# Connectors.net
KiCad netlist of a schematic drawn in Altium Designer
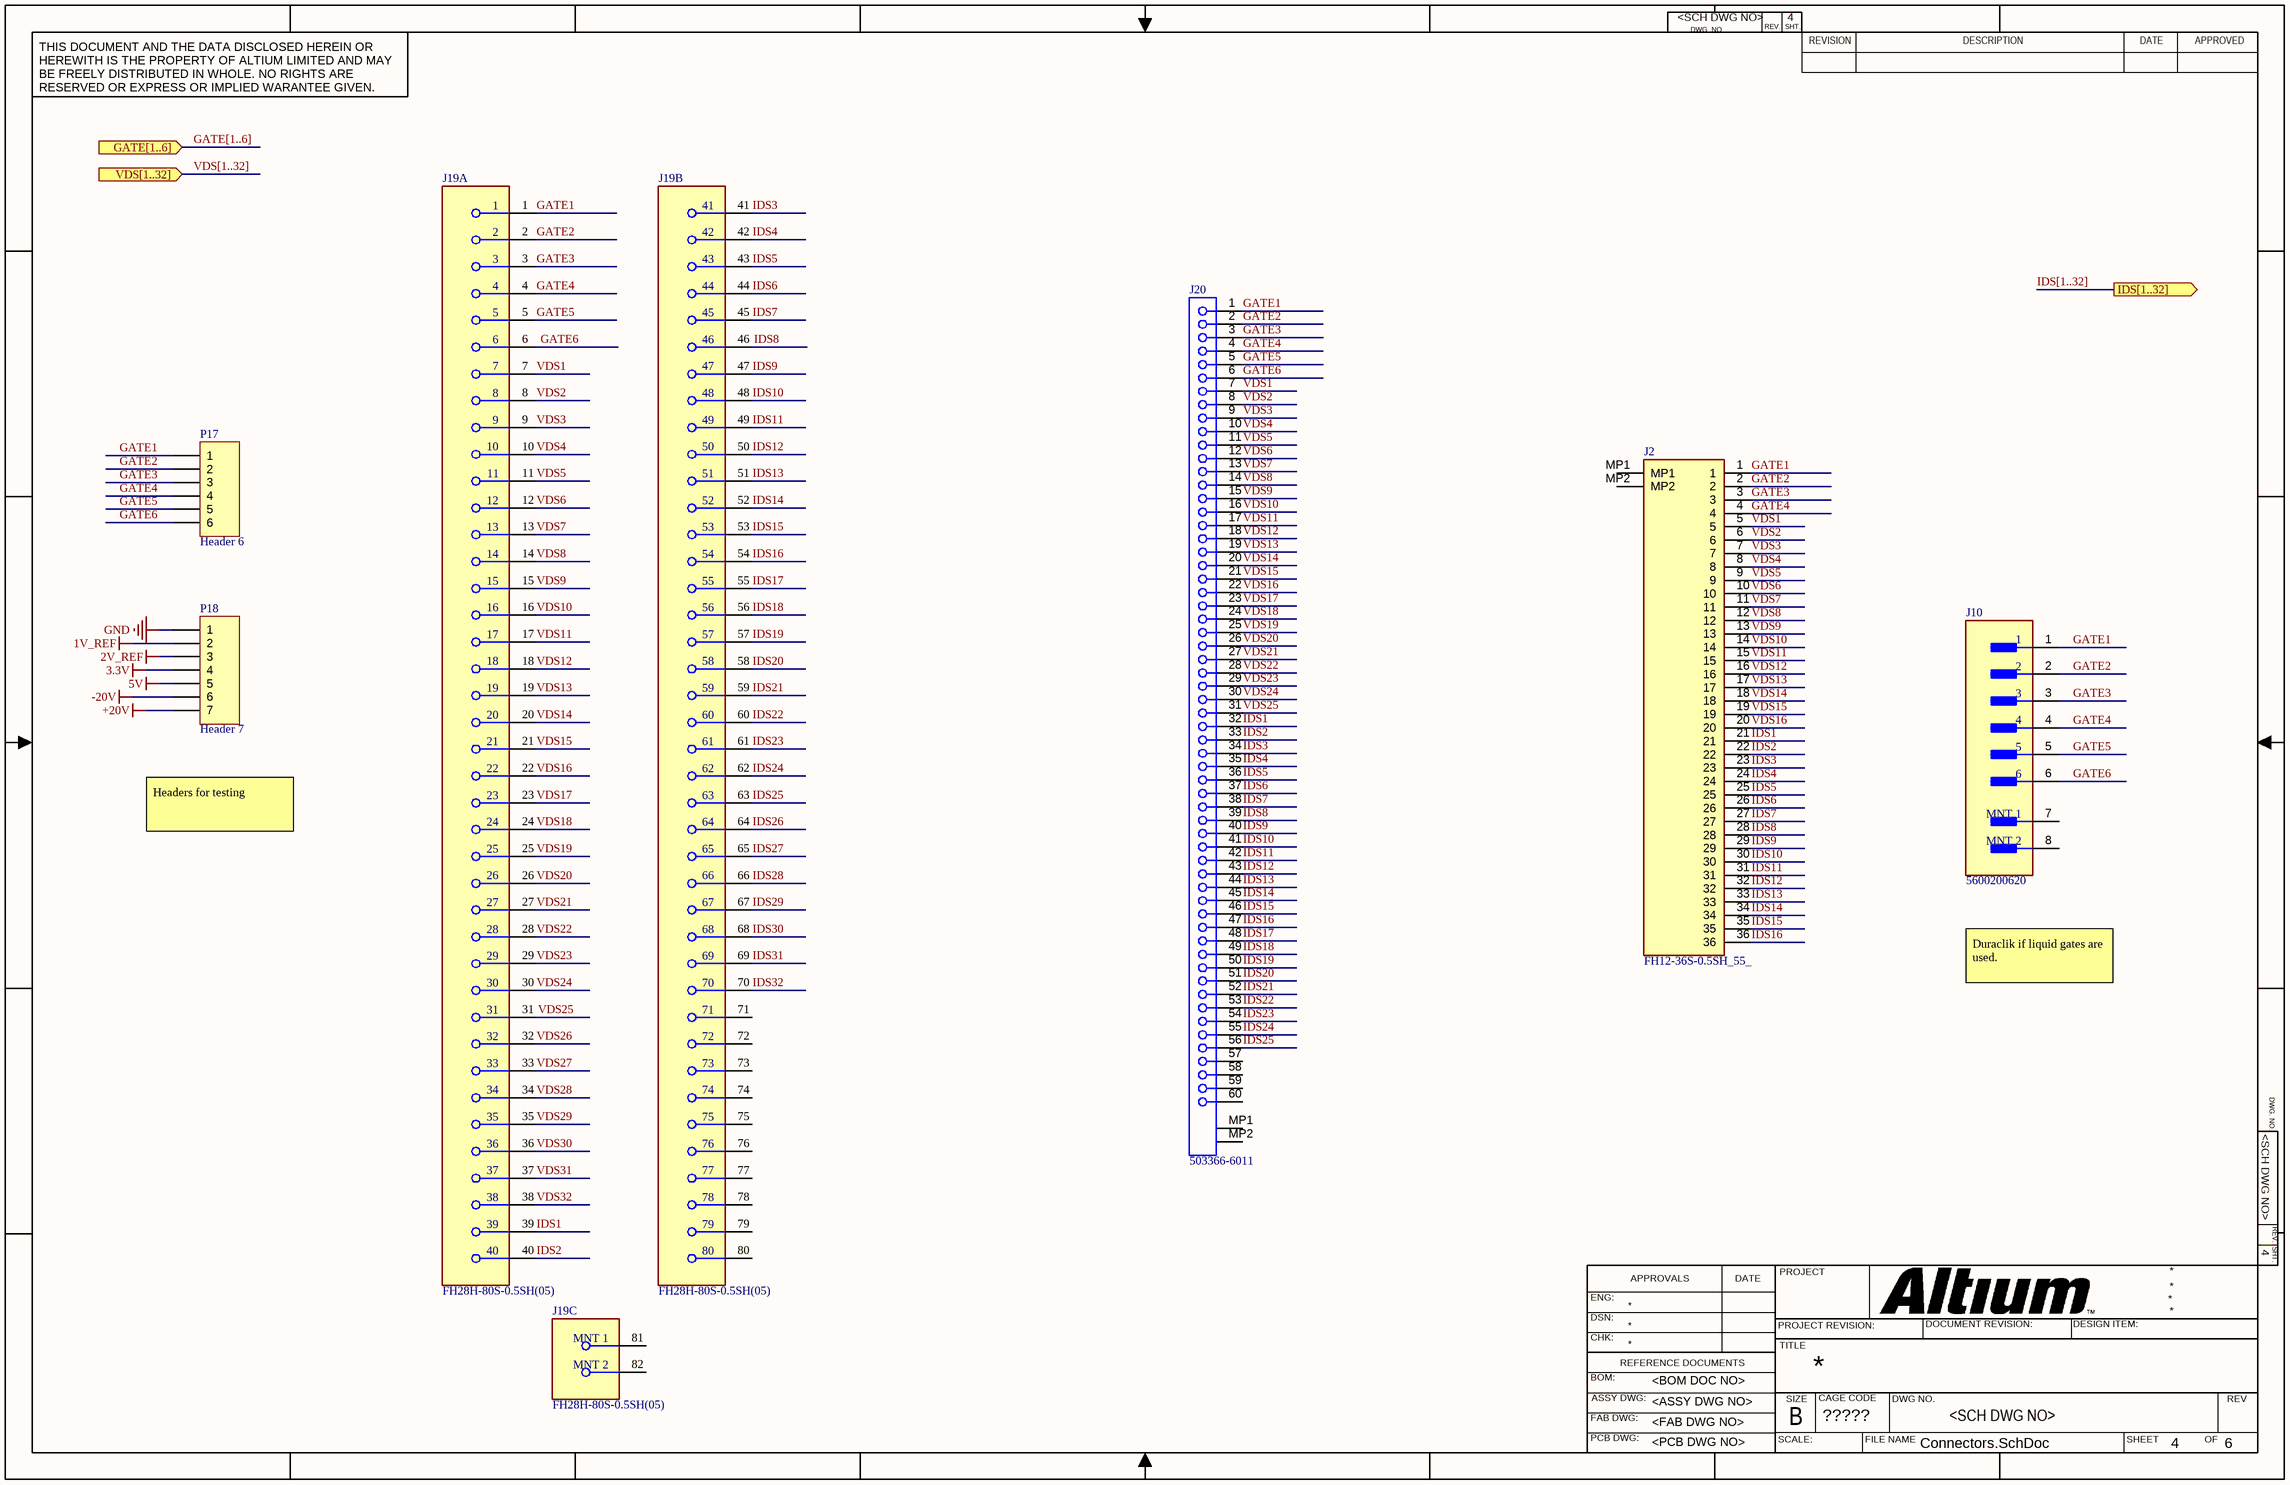
[diagram p0: Connectors.SchDoc]

(export (version "E")
  (design (tool "Eeschema 10.0.6"))
  (components
    (comp (ref "J2")
      (value "FH12-36S-0.5SH_55_")
      (footprint "FH1236S05SH55")
      (description "Connector")
      (fields
        (field (name "MANUFACTURER_PART_NUMBER") "FH12-36S-0.5SH(55)")
        (field (name "MOUSER PART NUMBER") "798-FH12-36S-0.5SH55")
      )
      (libsource (lib "SamacSys") (part "FH12-36S-0.5SH_55_"))
    )
    (comp (ref "J10")
      (value "5600200620")
      (footprint "FP-5600200620-MFG")
      (description "CONN HEADER SMD 6POS 2MM")
      (fields
        (field (name "OCTOPART") "https://octopart.com/5600200620-molex-51767481")
        (field (name "MANUFACTURER") "Molex")
      )
      (libsource (lib "Altium Content Vault") (part "ed24c53d9ba001d1a2a686240a95171"))
    )
    (comp (ref "J19")
      (value "FH28H-80S-0.5SH(05)")
      (footprint "FP-FH28H-80S-0_5SH_05-MFG")
      (description "CONN FFC BOTTOM 80POS 0.50MM R/A")
      (libsource (lib "Altium Content Vault") (part "08075b3669470a400ec152efcfe4938"))
    )
    (comp (ref "J20")
      (value "503366-6011")
      (footprint "MOLX-503366-6011")
      (fields (field (name "MANUFACTURER") "Molex"))
      (libsource (lib "Altium Content Vault") (part "MOLX-503366-6011"))
    )
    (comp (ref "P17")
      (value "Header 6")
      (footprint "HDR1X6")
      (description "Header, 6-Pin")
      (fields (field (name "PUBLISHER") "Altium Limited"))
      (libsource (lib "Miscellaneous Connectors") (part "Header 6"))
    )
    (comp (ref "P18")
      (value "Header 7")
      (footprint "HDR1X7")
      (description "Header, 7-Pin")
      (fields (field (name "PUBLISHER") "Altium Limited"))
      (libsource (lib "Miscellaneous Connectors") (part "Header 7"))
    )
  )
  (nets
    (net (code "1") (name "+20V") (class "Default")
      (node (ref "P18") (pin "7") (pinfunction "7_7") (pintype "passive"))
    )
    (net (code "2") (name "-20V") (class "Default")
      (node (ref "P18") (pin "6") (pinfunction "6_6") (pintype "passive"))
    )
    (net (code "3") (name "/GATE1") (class "Default")
      (node (ref "J10") (pin "1") (pinfunction "1_1") (pintype "passive"))
      (node (ref "J19") (pin "1") (pinfunction "1_1") (pintype "passive"))
      (node (ref "J2") (pin "1") (pinfunction "1_1") (pintype "passive"))
      (node (ref "J20") (pin "1") (pinfunction "1_1") (pintype "passive"))
      (node (ref "P17") (pin "1") (pinfunction "1_1") (pintype "passive"))
    )
    (net (code "4") (name "/GATE2") (class "Default")
      (node (ref "J10") (pin "2") (pinfunction "2_2") (pintype "passive"))
      (node (ref "J19") (pin "2") (pinfunction "2_2") (pintype "passive"))
      (node (ref "J2") (pin "2") (pinfunction "2_2") (pintype "passive"))
      (node (ref "J20") (pin "2") (pinfunction "2_2") (pintype "passive"))
      (node (ref "P17") (pin "2") (pinfunction "2_2") (pintype "passive"))
    )
    (net (code "5") (name "/GATE3") (class "Default")
      (node (ref "J10") (pin "3") (pinfunction "3_3") (pintype "passive"))
      (node (ref "J19") (pin "3") (pinfunction "3_3") (pintype "passive"))
      (node (ref "J2") (pin "3") (pinfunction "3_3") (pintype "passive"))
      (node (ref "J20") (pin "3") (pinfunction "3_3") (pintype "passive"))
      (node (ref "P17") (pin "3") (pinfunction "3_3") (pintype "passive"))
    )
    (net (code "6") (name "/GATE4") (class "Default")
      (node (ref "J10") (pin "4") (pinfunction "4_4") (pintype "passive"))
      (node (ref "J19") (pin "4") (pinfunction "4_4") (pintype "passive"))
      (node (ref "J2") (pin "4") (pinfunction "4_4") (pintype "passive"))
      (node (ref "J20") (pin "4") (pinfunction "4_4") (pintype "passive"))
      (node (ref "P17") (pin "4") (pinfunction "4_4") (pintype "passive"))
    )
    (net (code "7") (name "/GATE5") (class "Default")
      (node (ref "J10") (pin "5") (pinfunction "5_5") (pintype "passive"))
      (node (ref "J19") (pin "5") (pinfunction "5_5") (pintype "passive"))
      (node (ref "J20") (pin "5") (pinfunction "5_5") (pintype "passive"))
      (node (ref "P17") (pin "5") (pinfunction "5_5") (pintype "passive"))
    )
    (net (code "8") (name "/GATE6") (class "Default")
      (node (ref "J10") (pin "6") (pinfunction "6_6") (pintype "passive"))
      (node (ref "J19") (pin "6") (pinfunction "6_6") (pintype "passive"))
      (node (ref "J20") (pin "6") (pinfunction "6_6") (pintype "passive"))
      (node (ref "P17") (pin "6") (pinfunction "6_6") (pintype "passive"))
    )
    (net (code "10") (name "/IDS1") (class "Default")
      (node (ref "J19") (pin "39") (pinfunction "39_39") (pintype "passive"))
      (node (ref "J2") (pin "21") (pinfunction "21_21") (pintype "passive"))
      (node (ref "J20") (pin "32") (pinfunction "32_32") (pintype "passive"))
    )
    (net (code "11") (name "/IDS2") (class "Default")
      (node (ref "J19") (pin "40") (pinfunction "40_40") (pintype "passive"))
      (node (ref "J2") (pin "22") (pinfunction "22_22") (pintype "passive"))
      (node (ref "J20") (pin "33") (pinfunction "33_33") (pintype "passive"))
    )
    (net (code "12") (name "/IDS3") (class "Default")
      (node (ref "J19") (pin "41") (pinfunction "41_41") (pintype "passive"))
      (node (ref "J2") (pin "23") (pinfunction "23_23") (pintype "passive"))
      (node (ref "J20") (pin "34") (pinfunction "34_34") (pintype "passive"))
    )
    (net (code "13") (name "/IDS4") (class "Default")
      (node (ref "J19") (pin "42") (pinfunction "42_42") (pintype "passive"))
      (node (ref "J2") (pin "24") (pinfunction "24_24") (pintype "passive"))
      (node (ref "J20") (pin "35") (pinfunction "35_35") (pintype "passive"))
    )
    (net (code "14") (name "/IDS5") (class "Default")
      (node (ref "J19") (pin "43") (pinfunction "43_43") (pintype "passive"))
      (node (ref "J2") (pin "25") (pinfunction "25_25") (pintype "passive"))
      (node (ref "J20") (pin "36") (pinfunction "36_36") (pintype "passive"))
    )
    (net (code "15") (name "/IDS6") (class "Default")
      (node (ref "J19") (pin "44") (pinfunction "44_44") (pintype "passive"))
      (node (ref "J2") (pin "26") (pinfunction "26_26") (pintype "passive"))
      (node (ref "J20") (pin "37") (pinfunction "37_37") (pintype "passive"))
    )
    (net (code "16") (name "/IDS7") (class "Default")
      (node (ref "J19") (pin "45") (pinfunction "45_45") (pintype "passive"))
      (node (ref "J2") (pin "27") (pinfunction "27_27") (pintype "passive"))
      (node (ref "J20") (pin "38") (pinfunction "38_38") (pintype "passive"))
    )
    (net (code "17") (name "/IDS8") (class "Default")
      (node (ref "J19") (pin "46") (pinfunction "46_46") (pintype "passive"))
      (node (ref "J2") (pin "28") (pinfunction "28_28") (pintype "passive"))
      (node (ref "J20") (pin "39") (pinfunction "39_39") (pintype "passive"))
    )
    (net (code "18") (name "/IDS9") (class "Default")
      (node (ref "J19") (pin "47") (pinfunction "47_47") (pintype "passive"))
      (node (ref "J2") (pin "29") (pinfunction "29_29") (pintype "passive"))
      (node (ref "J20") (pin "40") (pinfunction "40_40") (pintype "passive"))
    )
    (net (code "19") (name "/IDS10") (class "Default")
      (node (ref "J19") (pin "48") (pinfunction "48_48") (pintype "passive"))
      (node (ref "J2") (pin "30") (pinfunction "30_30") (pintype "passive"))
      (node (ref "J20") (pin "41") (pinfunction "41_41") (pintype "passive"))
    )
    (net (code "20") (name "/IDS11") (class "Default")
      (node (ref "J19") (pin "49") (pinfunction "49_49") (pintype "passive"))
      (node (ref "J2") (pin "31") (pinfunction "31_31") (pintype "passive"))
      (node (ref "J20") (pin "42") (pinfunction "42_42") (pintype "passive"))
    )
    (net (code "21") (name "/IDS12") (class "Default")
      (node (ref "J19") (pin "50") (pinfunction "50_50") (pintype "passive"))
      (node (ref "J2") (pin "32") (pinfunction "32_32") (pintype "passive"))
      (node (ref "J20") (pin "43") (pinfunction "43_43") (pintype "passive"))
    )
    (net (code "22") (name "/IDS13") (class "Default")
      (node (ref "J19") (pin "51") (pinfunction "51_51") (pintype "passive"))
      (node (ref "J2") (pin "33") (pinfunction "33_33") (pintype "passive"))
      (node (ref "J20") (pin "44") (pinfunction "44_44") (pintype "passive"))
    )
    (net (code "23") (name "/IDS14") (class "Default")
      (node (ref "J19") (pin "52") (pinfunction "52_52") (pintype "passive"))
      (node (ref "J2") (pin "34") (pinfunction "34_34") (pintype "passive"))
      (node (ref "J20") (pin "45") (pinfunction "45_45") (pintype "passive"))
    )
    (net (code "24") (name "/IDS15") (class "Default")
      (node (ref "J19") (pin "53") (pinfunction "53_53") (pintype "passive"))
      (node (ref "J2") (pin "35") (pinfunction "35_35") (pintype "passive"))
      (node (ref "J20") (pin "46") (pinfunction "46_46") (pintype "passive"))
    )
    (net (code "25") (name "/IDS16") (class "Default")
      (node (ref "J19") (pin "54") (pinfunction "54_54") (pintype "passive"))
      (node (ref "J2") (pin "36") (pinfunction "36_36") (pintype "passive"))
      (node (ref "J20") (pin "47") (pinfunction "47_47") (pintype "passive"))
    )
    (net (code "26") (name "/IDS17") (class "Default")
      (node (ref "J19") (pin "55") (pinfunction "55_55") (pintype "passive"))
      (node (ref "J20") (pin "48") (pinfunction "48_48") (pintype "passive"))
    )
    (net (code "27") (name "/IDS18") (class "Default")
      (node (ref "J19") (pin "56") (pinfunction "56_56") (pintype "passive"))
      (node (ref "J20") (pin "49") (pinfunction "49_49") (pintype "passive"))
    )
    (net (code "28") (name "/IDS19") (class "Default")
      (node (ref "J19") (pin "57") (pinfunction "57_57") (pintype "passive"))
      (node (ref "J20") (pin "50") (pinfunction "50_50") (pintype "passive"))
    )
    (net (code "29") (name "/IDS20") (class "Default")
      (node (ref "J19") (pin "58") (pinfunction "58_58") (pintype "passive"))
      (node (ref "J20") (pin "51") (pinfunction "51_51") (pintype "passive"))
    )
    (net (code "30") (name "/IDS21") (class "Default")
      (node (ref "J19") (pin "59") (pinfunction "59_59") (pintype "passive"))
      (node (ref "J20") (pin "52") (pinfunction "52_52") (pintype "passive"))
    )
    (net (code "31") (name "/IDS22") (class "Default")
      (node (ref "J19") (pin "60") (pinfunction "60_60") (pintype "passive"))
      (node (ref "J20") (pin "53") (pinfunction "53_53") (pintype "passive"))
    )
    (net (code "32") (name "/IDS23") (class "Default")
      (node (ref "J19") (pin "61") (pinfunction "61_61") (pintype "passive"))
      (node (ref "J20") (pin "54") (pinfunction "54_54") (pintype "passive"))
    )
    (net (code "33") (name "/IDS24") (class "Default")
      (node (ref "J19") (pin "62") (pinfunction "62_62") (pintype "passive"))
      (node (ref "J20") (pin "55") (pinfunction "55_55") (pintype "passive"))
    )
    (net (code "34") (name "/IDS25") (class "Default")
      (node (ref "J19") (pin "63") (pinfunction "63_63") (pintype "passive"))
      (node (ref "J20") (pin "56") (pinfunction "56_56") (pintype "passive"))
    )
    (net (code "35") (name "/IDS26") (class "Default")
      (node (ref "J19") (pin "64") (pinfunction "64_64") (pintype "passive"))
    )
    (net (code "36") (name "/IDS27") (class "Default")
      (node (ref "J19") (pin "65") (pinfunction "65_65") (pintype "passive"))
    )
    (net (code "37") (name "/IDS28") (class "Default")
      (node (ref "J19") (pin "66") (pinfunction "66_66") (pintype "passive"))
    )
    (net (code "38") (name "/IDS29") (class "Default")
      (node (ref "J19") (pin "67") (pinfunction "67_67") (pintype "passive"))
    )
    (net (code "39") (name "/IDS30") (class "Default")
      (node (ref "J19") (pin "68") (pinfunction "68_68") (pintype "passive"))
    )
    (net (code "40") (name "/IDS31") (class "Default")
      (node (ref "J19") (pin "69") (pinfunction "69_69") (pintype "passive"))
    )
    (net (code "41") (name "/IDS32") (class "Default")
      (node (ref "J19") (pin "70") (pinfunction "70_70") (pintype "passive"))
    )
    (net (code "43") (name "/VDS1") (class "Default")
      (node (ref "J19") (pin "7") (pinfunction "7_7") (pintype "passive"))
      (node (ref "J2") (pin "5") (pinfunction "5_5") (pintype "passive"))
      (node (ref "J20") (pin "7") (pinfunction "7_7") (pintype "passive"))
    )
    (net (code "44") (name "/VDS2") (class "Default")
      (node (ref "J19") (pin "8") (pinfunction "8_8") (pintype "passive"))
      (node (ref "J2") (pin "6") (pinfunction "6_6") (pintype "passive"))
      (node (ref "J20") (pin "8") (pinfunction "8_8") (pintype "passive"))
    )
    (net (code "45") (name "/VDS3") (class "Default")
      (node (ref "J19") (pin "9") (pinfunction "9_9") (pintype "passive"))
      (node (ref "J2") (pin "7") (pinfunction "7_7") (pintype "passive"))
      (node (ref "J20") (pin "9") (pinfunction "9_9") (pintype "passive"))
    )
    (net (code "46") (name "/VDS4") (class "Default")
      (node (ref "J19") (pin "10") (pinfunction "10_10") (pintype "passive"))
      (node (ref "J2") (pin "8") (pinfunction "8_8") (pintype "passive"))
      (node (ref "J20") (pin "10") (pinfunction "10_10") (pintype "passive"))
    )
    (net (code "47") (name "/VDS5") (class "Default")
      (node (ref "J19") (pin "11") (pinfunction "11_11") (pintype "passive"))
      (node (ref "J2") (pin "9") (pinfunction "9_9") (pintype "passive"))
      (node (ref "J20") (pin "11") (pinfunction "11_11") (pintype "passive"))
    )
    (net (code "48") (name "/VDS6") (class "Default")
      (node (ref "J19") (pin "12") (pinfunction "12_12") (pintype "passive"))
      (node (ref "J2") (pin "10") (pinfunction "10_10") (pintype "passive"))
      (node (ref "J20") (pin "12") (pinfunction "12_12") (pintype "passive"))
    )
    (net (code "49") (name "/VDS7") (class "Default")
      (node (ref "J19") (pin "13") (pinfunction "13_13") (pintype "passive"))
      (node (ref "J2") (pin "11") (pinfunction "11_11") (pintype "passive"))
      (node (ref "J20") (pin "13") (pinfunction "13_13") (pintype "passive"))
    )
    (net (code "50") (name "/VDS8") (class "Default")
      (node (ref "J19") (pin "14") (pinfunction "14_14") (pintype "passive"))
      (node (ref "J2") (pin "12") (pinfunction "12_12") (pintype "passive"))
      (node (ref "J20") (pin "14") (pinfunction "14_14") (pintype "passive"))
    )
    (net (code "51") (name "/VDS9") (class "Default")
      (node (ref "J19") (pin "15") (pinfunction "15_15") (pintype "passive"))
      (node (ref "J2") (pin "13") (pinfunction "13_13") (pintype "passive"))
      (node (ref "J20") (pin "15") (pinfunction "15_15") (pintype "passive"))
    )
    (net (code "52") (name "/VDS10") (class "Default")
      (node (ref "J19") (pin "16") (pinfunction "16_16") (pintype "passive"))
      (node (ref "J2") (pin "14") (pinfunction "14_14") (pintype "passive"))
      (node (ref "J20") (pin "16") (pinfunction "16_16") (pintype "passive"))
    )
    (net (code "53") (name "/VDS11") (class "Default")
      (node (ref "J19") (pin "17") (pinfunction "17_17") (pintype "passive"))
      (node (ref "J2") (pin "15") (pinfunction "15_15") (pintype "passive"))
      (node (ref "J20") (pin "17") (pinfunction "17_17") (pintype "passive"))
    )
    (net (code "54") (name "/VDS12") (class "Default")
      (node (ref "J19") (pin "18") (pinfunction "18_18") (pintype "passive"))
      (node (ref "J2") (pin "16") (pinfunction "16_16") (pintype "passive"))
      (node (ref "J20") (pin "18") (pinfunction "18_18") (pintype "passive"))
    )
    (net (code "55") (name "/VDS13") (class "Default")
      (node (ref "J19") (pin "19") (pinfunction "19_19") (pintype "passive"))
      (node (ref "J2") (pin "17") (pinfunction "17_17") (pintype "passive"))
      (node (ref "J20") (pin "19") (pinfunction "19_19") (pintype "passive"))
    )
    (net (code "56") (name "/VDS14") (class "Default")
      (node (ref "J19") (pin "20") (pinfunction "20_20") (pintype "passive"))
      (node (ref "J2") (pin "18") (pinfunction "18_18") (pintype "passive"))
      (node (ref "J20") (pin "20") (pinfunction "20_20") (pintype "passive"))
    )
    (net (code "57") (name "/VDS15") (class "Default")
      (node (ref "J19") (pin "21") (pinfunction "21_21") (pintype "passive"))
      (node (ref "J2") (pin "19") (pinfunction "19_19") (pintype "passive"))
      (node (ref "J20") (pin "21") (pinfunction "21_21") (pintype "passive"))
    )
    (net (code "58") (name "/VDS16") (class "Default")
      (node (ref "J19") (pin "22") (pinfunction "22_22") (pintype "passive"))
      (node (ref "J2") (pin "20") (pinfunction "20_20") (pintype "passive"))
      (node (ref "J20") (pin "22") (pinfunction "22_22") (pintype "passive"))
    )
    (net (code "59") (name "/VDS17") (class "Default")
      (node (ref "J19") (pin "23") (pinfunction "23_23") (pintype "passive"))
      (node (ref "J20") (pin "23") (pinfunction "23_23") (pintype "passive"))
    )
    (net (code "60") (name "/VDS18") (class "Default")
      (node (ref "J19") (pin "24") (pinfunction "24_24") (pintype "passive"))
      (node (ref "J20") (pin "24") (pinfunction "24_24") (pintype "passive"))
    )
    (net (code "61") (name "/VDS19") (class "Default")
      (node (ref "J19") (pin "25") (pinfunction "25_25") (pintype "passive"))
      (node (ref "J20") (pin "25") (pinfunction "25_25") (pintype "passive"))
    )
    (net (code "62") (name "/VDS20") (class "Default")
      (node (ref "J19") (pin "26") (pinfunction "26_26") (pintype "passive"))
      (node (ref "J20") (pin "26") (pinfunction "26_26") (pintype "passive"))
    )
    (net (code "63") (name "/VDS21") (class "Default")
      (node (ref "J19") (pin "27") (pinfunction "27_27") (pintype "passive"))
      (node (ref "J20") (pin "27") (pinfunction "27_27") (pintype "passive"))
    )
    (net (code "64") (name "/VDS22") (class "Default")
      (node (ref "J19") (pin "28") (pinfunction "28_28") (pintype "passive"))
      (node (ref "J20") (pin "28") (pinfunction "28_28") (pintype "passive"))
    )
    (net (code "65") (name "/VDS23") (class "Default")
      (node (ref "J19") (pin "29") (pinfunction "29_29") (pintype "passive"))
      (node (ref "J20") (pin "29") (pinfunction "29_29") (pintype "passive"))
    )
    (net (code "66") (name "/VDS24") (class "Default")
      (node (ref "J19") (pin "30") (pinfunction "30_30") (pintype "passive"))
      (node (ref "J20") (pin "30") (pinfunction "30_30") (pintype "passive"))
    )
    (net (code "67") (name "/VDS25") (class "Default")
      (node (ref "J19") (pin "31") (pinfunction "31_31") (pintype "passive"))
      (node (ref "J20") (pin "31") (pinfunction "31_31") (pintype "passive"))
    )
    (net (code "68") (name "/VDS26") (class "Default")
      (node (ref "J19") (pin "32") (pinfunction "32_32") (pintype "passive"))
    )
    (net (code "69") (name "/VDS27") (class "Default")
      (node (ref "J19") (pin "33") (pinfunction "33_33") (pintype "passive"))
    )
    (net (code "70") (name "/VDS28") (class "Default")
      (node (ref "J19") (pin "34") (pinfunction "34_34") (pintype "passive"))
    )
    (net (code "71") (name "/VDS29") (class "Default")
      (node (ref "J19") (pin "35") (pinfunction "35_35") (pintype "passive"))
    )
    (net (code "72") (name "/VDS30") (class "Default")
      (node (ref "J19") (pin "36") (pinfunction "36_36") (pintype "passive"))
    )
    (net (code "73") (name "/VDS31") (class "Default")
      (node (ref "J19") (pin "37") (pinfunction "37_37") (pintype "passive"))
    )
    (net (code "74") (name "/VDS32") (class "Default")
      (node (ref "J19") (pin "38") (pinfunction "38_38") (pintype "passive"))
    )
    (net (code "76") (name "1V_REF") (class "Default")
      (node (ref "P18") (pin "2") (pinfunction "2_2") (pintype "passive"))
    )
    (net (code "77") (name "2V_REF") (class "Default")
      (node (ref "P18") (pin "3") (pinfunction "3_3") (pintype "passive"))
    )
    (net (code "78") (name "3.3V") (class "Default")
      (node (ref "P18") (pin "4") (pinfunction "4_4") (pintype "passive"))
    )
    (net (code "79") (name "5V") (class "Default")
      (node (ref "P18") (pin "5") (pinfunction "5_5") (pintype "passive"))
    )
    (net (code "80") (name "GND") (class "Default")
      (node (ref "P18") (pin "1") (pinfunction "1_1") (pintype "passive"))
    )
    (net (code "81") (name "unconnected-(J2-PadMP1)") (class "Default")
      (node (ref "J2") (pin "MP1") (pinfunction "MP1_MP1") (pintype "passive"))
    )
    (net (code "82") (name "unconnected-(J2-PadMP2)") (class "Default")
      (node (ref "J2") (pin "MP2") (pinfunction "MP2_MP2") (pintype "passive"))
    )
    (net (code "83") (name "unconnected-(J10-MNT_1-Pad7)") (class "Default")
      (node (ref "J10") (pin "7") (pinfunction "MNT_1_7") (pintype "passive"))
    )
    (net (code "84") (name "unconnected-(J10-MNT_2-Pad8)") (class "Default")
      (node (ref "J10") (pin "8") (pinfunction "MNT_2_8") (pintype "passive"))
    )
    (net (code "85") (name "unconnected-(J19-Pad71)") (class "Default")
      (node (ref "J19") (pin "71") (pinfunction "71_71") (pintype "passive"))
    )
    (net (code "86") (name "unconnected-(J19-Pad72)") (class "Default")
      (node (ref "J19") (pin "72") (pinfunction "72_72") (pintype "passive"))
    )
    (net (code "87") (name "unconnected-(J19-Pad73)") (class "Default")
      (node (ref "J19") (pin "73") (pinfunction "73_73") (pintype "passive"))
    )
    (net (code "88") (name "unconnected-(J19-Pad74)") (class "Default")
      (node (ref "J19") (pin "74") (pinfunction "74_74") (pintype "passive"))
    )
    (net (code "89") (name "unconnected-(J19-Pad75)") (class "Default")
      (node (ref "J19") (pin "75") (pinfunction "75_75") (pintype "passive"))
    )
    (net (code "90") (name "unconnected-(J19-Pad76)") (class "Default")
      (node (ref "J19") (pin "76") (pinfunction "76_76") (pintype "passive"))
    )
    (net (code "91") (name "unconnected-(J19-Pad77)") (class "Default")
      (node (ref "J19") (pin "77") (pinfunction "77_77") (pintype "passive"))
    )
    (net (code "92") (name "unconnected-(J19-Pad78)") (class "Default")
      (node (ref "J19") (pin "78") (pinfunction "78_78") (pintype "passive"))
    )
    (net (code "93") (name "unconnected-(J19-Pad79)") (class "Default")
      (node (ref "J19") (pin "79") (pinfunction "79_79") (pintype "passive"))
    )
    (net (code "94") (name "unconnected-(J19-Pad80)") (class "Default")
      (node (ref "J19") (pin "80") (pinfunction "80_80") (pintype "passive"))
    )
    (net (code "95") (name "unconnected-(J19C-MNT_1-Pad81)") (class "Default")
      (node (ref "J19") (pin "81") (pinfunction "MNT_1_81") (pintype "passive"))
    )
    (net (code "96") (name "unconnected-(J19C-MNT_2-Pad82)") (class "Default")
      (node (ref "J19") (pin "82") (pinfunction "MNT_2_82") (pintype "passive"))
    )
    (net (code "97") (name "unconnected-(J20-Pad57)") (class "Default")
      (node (ref "J20") (pin "57") (pinfunction "57_57") (pintype "passive"))
    )
    (net (code "98") (name "unconnected-(J20-Pad58)") (class "Default")
      (node (ref "J20") (pin "58") (pinfunction "58_58") (pintype "passive"))
    )
    (net (code "99") (name "unconnected-(J20-Pad59)") (class "Default")
      (node (ref "J20") (pin "59") (pinfunction "59_59") (pintype "passive"))
    )
    (net (code "100") (name "unconnected-(J20-Pad60)") (class "Default")
      (node (ref "J20") (pin "60") (pinfunction "60_60") (pintype "passive"))
    )
    (net (code "101") (name "unconnected-(J20-PadMP1)") (class "Default")
      (node (ref "J20") (pin "MP1") (pinfunction "MP1_MP1") (pintype "passive"))
    )
    (net (code "102") (name "unconnected-(J20-PadMP2)") (class "Default")
      (node (ref "J20") (pin "MP2") (pinfunction "MP2_MP2") (pintype "passive"))
    )
  )
)
